# Taster.net
KiCad netlist of a schematic drawn in EAGLE
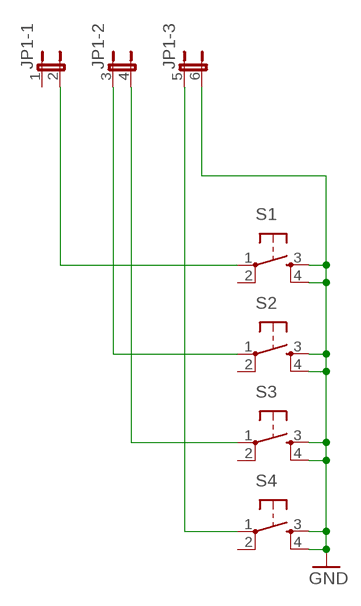
[diagram p0: schematic, sheet 1]

(export (version "E")
  (design (tool "Eeschema 10.0.6"))
  (components
    (comp (ref "JP1")
      (value "JP3QE")
      (footprint "eagle-import:JP3Q")
      (libsource (lib "eagle-import") (part "JP3QE"))
    )
    (comp (ref "S1")
      (value "TAC_SWITCHPTH")
      (footprint "eagle-import:TACTILE-PTH")
      (libsource (lib "eagle-import") (part "TAC_SWITCHPTH"))
    )
    (comp (ref "S2")
      (value "TAC_SWITCHPTH")
      (footprint "eagle-import:TACTILE-PTH")
      (libsource (lib "eagle-import") (part "TAC_SWITCHPTH"))
    )
    (comp (ref "S3")
      (value "TAC_SWITCHPTH")
      (footprint "eagle-import:TACTILE-PTH")
      (libsource (lib "eagle-import") (part "TAC_SWITCHPTH"))
    )
    (comp (ref "S4")
      (value "TAC_SWITCHPTH")
      (footprint "eagle-import:TACTILE-PTH")
      (libsource (lib "eagle-import") (part "TAC_SWITCHPTH"))
    )
  )
  (nets
    (net (code "1") (name "GND") (class "Default")
      (node (ref "JP1") (pin "6") (pinfunction "2_6") (pintype "passive"))
      (node (ref "S1") (pin "3") (pinfunction "3_3") (pintype "passive"))
      (node (ref "S1") (pin "4") (pinfunction "4_4") (pintype "passive"))
      (node (ref "S2") (pin "3") (pinfunction "3_3") (pintype "passive"))
      (node (ref "S2") (pin "4") (pinfunction "4_4") (pintype "passive"))
      (node (ref "S3") (pin "3") (pinfunction "3_3") (pintype "passive"))
      (node (ref "S3") (pin "4") (pinfunction "4_4") (pintype "passive"))
      (node (ref "S4") (pin "3") (pinfunction "3_3") (pintype "passive"))
      (node (ref "S4") (pin "4") (pinfunction "4_4") (pintype "passive"))
    )
    (net (code "2") (name "Net-(JP1-Pad2)") (class "Default")
      (node (ref "JP1") (pin "2") (pinfunction "2_2") (pintype "passive"))
      (node (ref "S1") (pin "1") (pinfunction "1_1") (pintype "passive"))
    )
    (net (code "3") (name "Net-(JP1B-1)") (class "Default")
      (node (ref "JP1") (pin "3") (pinfunction "1_3") (pintype "passive"))
      (node (ref "S2") (pin "1") (pinfunction "1_1") (pintype "passive"))
    )
    (net (code "4") (name "Net-(JP1B-2)") (class "Default")
      (node (ref "JP1") (pin "4") (pinfunction "2_4") (pintype "passive"))
      (node (ref "S3") (pin "1") (pinfunction "1_1") (pintype "passive"))
    )
    (net (code "5") (name "Net-(JP1C-1)") (class "Default")
      (node (ref "JP1") (pin "5") (pinfunction "1_5") (pintype "passive"))
      (node (ref "S4") (pin "1") (pinfunction "1_1") (pintype "passive"))
    )
    (net (code "6") (name "unconnected-(JP1-Pad1)") (class "Default")
      (node (ref "JP1") (pin "1") (pinfunction "1_1") (pintype "passive"))
    )
    (net (code "7") (name "unconnected-(S1-Pad2)") (class "Default")
      (node (ref "S1") (pin "2") (pinfunction "2_2") (pintype "passive"))
    )
    (net (code "8") (name "unconnected-(S2-Pad2)") (class "Default")
      (node (ref "S2") (pin "2") (pinfunction "2_2") (pintype "passive"))
    )
    (net (code "9") (name "unconnected-(S3-Pad2)") (class "Default")
      (node (ref "S3") (pin "2") (pinfunction "2_2") (pintype "passive"))
    )
    (net (code "10") (name "unconnected-(S4-Pad2)") (class "Default")
      (node (ref "S4") (pin "2") (pinfunction "2_2") (pintype "passive"))
    )
  )
)
